# facebard-7-sensor-neopixel-ffc.net
KiCad netlist of a schematic drawn in EAGLE
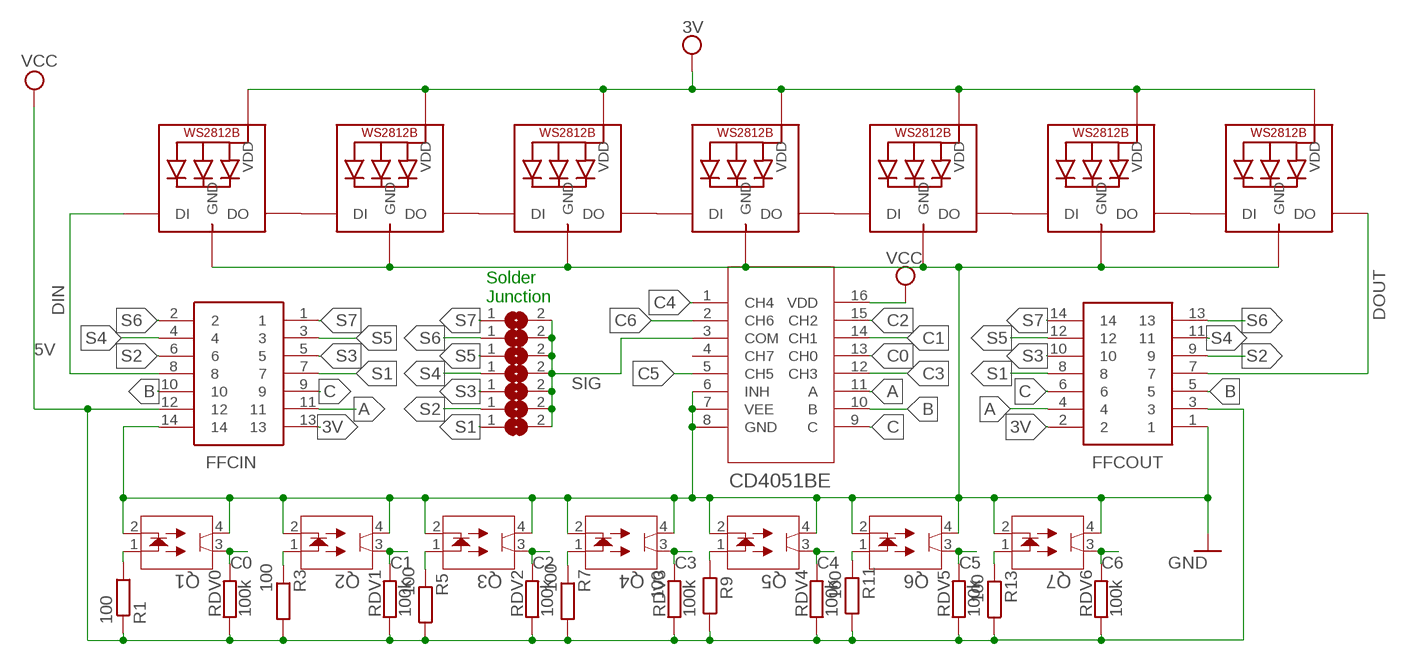
[diagram p0: schematic, sheet 1]

(export (version "E")
  (design (tool "Eeschema 10.0.6"))
  (components
    (comp (ref "FFCIN")
      (value "52806-1410")
      (footprint "eagle-import:528061410")
      (fields (field (name "MOUSER_PART_NUMBER") "538-52806-1410"))
      (libsource (lib "eagle-import") (part "52806-1410"))
    )
    (comp (ref "FFCOUT")
      (value "52806-1410")
      (footprint "eagle-import:528061410")
      (fields (field (name "MOUSER_PART_NUMBER") "538-52806-1410"))
      (libsource (lib "eagle-import") (part "52806-1410"))
    )
    (comp (ref "LED1")
      (value "WS2812B3535")
      (footprint "eagle-import:LED3535")
      (libsource (lib "eagle-import") (part "WS2812B3535"))
    )
    (comp (ref "LED2")
      (value "WS2812B3535")
      (footprint "eagle-import:LED3535")
      (libsource (lib "eagle-import") (part "WS2812B3535"))
    )
    (comp (ref "LED3")
      (value "WS2812B3535")
      (footprint "eagle-import:LED3535")
      (libsource (lib "eagle-import") (part "WS2812B3535"))
    )
    (comp (ref "LED4")
      (value "WS2812B3535")
      (footprint "eagle-import:LED3535")
      (libsource (lib "eagle-import") (part "WS2812B3535"))
    )
    (comp (ref "LED5")
      (value "WS2812B3535")
      (footprint "eagle-import:LED3535")
      (libsource (lib "eagle-import") (part "WS2812B3535"))
    )
    (comp (ref "LED6")
      (value "WS2812B3535")
      (footprint "eagle-import:LED3535")
      (libsource (lib "eagle-import") (part "WS2812B3535"))
    )
    (comp (ref "LED7")
      (value "WS2812B3535")
      (footprint "eagle-import:LED3535")
      (libsource (lib "eagle-import") (part "WS2812B3535"))
    )
    (comp (ref "Q1")
      (value "QRE1113")
      (footprint "eagle-import:DIP4_100AQ_ONS")
      (fields (field (name "COPYRIGHT") "Copyright (C) 2024 Ultra Librarian. All rights reserved."))
      (libsource (lib "eagle-import") (part "QRE1113"))
    )
    (comp (ref "Q2")
      (value "QRE1113")
      (footprint "eagle-import:DIP4_100AQ_ONS")
      (fields (field (name "COPYRIGHT") "Copyright (C) 2024 Ultra Librarian. All rights reserved."))
      (libsource (lib "eagle-import") (part "QRE1113"))
    )
    (comp (ref "Q3")
      (value "QRE1113")
      (footprint "eagle-import:DIP4_100AQ_ONS")
      (fields (field (name "COPYRIGHT") "Copyright (C) 2024 Ultra Librarian. All rights reserved."))
      (libsource (lib "eagle-import") (part "QRE1113"))
    )
    (comp (ref "Q4")
      (value "QRE1113")
      (footprint "eagle-import:DIP4_100AQ_ONS")
      (fields (field (name "COPYRIGHT") "Copyright (C) 2024 Ultra Librarian. All rights reserved."))
      (libsource (lib "eagle-import") (part "QRE1113"))
    )
    (comp (ref "Q5")
      (value "QRE1113")
      (footprint "eagle-import:DIP4_100AQ_ONS")
      (fields (field (name "COPYRIGHT") "Copyright (C) 2024 Ultra Librarian. All rights reserved."))
      (libsource (lib "eagle-import") (part "QRE1113"))
    )
    (comp (ref "Q6")
      (value "QRE1113")
      (footprint "eagle-import:DIP4_100AQ_ONS")
      (fields (field (name "COPYRIGHT") "Copyright (C) 2024 Ultra Librarian. All rights reserved."))
      (libsource (lib "eagle-import") (part "QRE1113"))
    )
    (comp (ref "Q7")
      (value "QRE1113")
      (footprint "eagle-import:DIP4_100AQ_ONS")
      (fields (field (name "COPYRIGHT") "Copyright (C) 2024 Ultra Librarian. All rights reserved."))
      (libsource (lib "eagle-import") (part "QRE1113"))
    )
    (comp (ref "R1")
      (value "100")
      (footprint "eagle-import:0207_10")
      (libsource (lib "eagle-import") (part "R-EU_0207/10"))
    )
    (comp (ref "R3")
      (value "100")
      (footprint "eagle-import:0207_10")
      (libsource (lib "eagle-import") (part "R-EU_0207/10"))
    )
    (comp (ref "R5")
      (value "100")
      (footprint "eagle-import:0207_10")
      (libsource (lib "eagle-import") (part "R-EU_0207/10"))
    )
    (comp (ref "R7")
      (value "100")
      (footprint "eagle-import:0207_10")
      (libsource (lib "eagle-import") (part "R-EU_0207/10"))
    )
    (comp (ref "R9")
      (value "100")
      (footprint "eagle-import:0207_10")
      (libsource (lib "eagle-import") (part "R-EU_0207/10"))
    )
    (comp (ref "R11")
      (value "100")
      (footprint "eagle-import:0207_10")
      (libsource (lib "eagle-import") (part "R-EU_0207/10"))
    )
    (comp (ref "R13")
      (value "100")
      (footprint "eagle-import:0207_10")
      (libsource (lib "eagle-import") (part "R-EU_0207/10"))
    )
    (comp (ref "RDV0")
      (value "100k")
      (footprint "eagle-import:0207_10")
      (libsource (lib "eagle-import") (part "R-EU_0207/10"))
    )
    (comp (ref "RDV1")
      (value "100k")
      (footprint "eagle-import:0207_10")
      (libsource (lib "eagle-import") (part "R-EU_0207/10"))
    )
    (comp (ref "RDV2")
      (value "100k")
      (footprint "eagle-import:0207_10")
      (libsource (lib "eagle-import") (part "R-EU_0207/10"))
    )
    (comp (ref "RDV3")
      (value "100k")
      (footprint "eagle-import:0207_10")
      (libsource (lib "eagle-import") (part "R-EU_0207/10"))
    )
    (comp (ref "RDV4")
      (value "100k")
      (footprint "eagle-import:0207_10")
      (libsource (lib "eagle-import") (part "R-EU_0207/10"))
    )
    (comp (ref "RDV5")
      (value "100k")
      (footprint "eagle-import:0207_10")
      (libsource (lib "eagle-import") (part "R-EU_0207/10"))
    )
    (comp (ref "RDV6")
      (value "100k")
      (footprint "eagle-import:0207_10")
      (libsource (lib "eagle-import") (part "R-EU_0207/10"))
    )
    (comp (ref "SJ1") (value "SJ") (footprint "eagle-import:SJ") (libsource (lib "eagle-import") (part "SJ")))
    (comp (ref "SJ2") (value "SJ") (footprint "eagle-import:SJ") (libsource (lib "eagle-import") (part "SJ")))
    (comp (ref "SJ3") (value "SJ") (footprint "eagle-import:SJ") (libsource (lib "eagle-import") (part "SJ")))
    (comp (ref "SJ4") (value "SJ") (footprint "eagle-import:SJ") (libsource (lib "eagle-import") (part "SJ")))
    (comp (ref "SJ5") (value "SJ") (footprint "eagle-import:SJ") (libsource (lib "eagle-import") (part "SJ")))
    (comp (ref "SJ6") (value "SJ") (footprint "eagle-import:SJ") (libsource (lib "eagle-import") (part "SJ")))
    (comp (ref "SJ7") (value "SJ") (footprint "eagle-import:SJ") (libsource (lib "eagle-import") (part "SJ")))
    (comp (ref "U1")
      (value "CD4051BE")
      (footprint "eagle-import:N16")
      (fields (field (name "COPYRIGHT") "Copyright (C) 2024 Ultra Librarian. All rights reserved."))
      (libsource (lib "eagle-import") (part "CD4051BE"))
    )
  )
  (nets
    (net (code "1") (name "/DIN") (class "Default")
      (node (ref "FFCIN") (pin "8") (pinfunction "8_8") (pintype "bidirectional"))
      (node (ref "LED1") (pin "1") (pinfunction "DI_1") (pintype "input"))
    )
    (net (code "2") (name "/DOUT") (class "Default")
      (node (ref "FFCOUT") (pin "7") (pinfunction "7_7") (pintype "bidirectional"))
      (node (ref "LED7") (pin "3") (pinfunction "DO_3") (pintype "output"))
    )
    (net (code "3") (name "/SIG") (class "Default")
      (node (ref "SJ1") (pin "2") (pinfunction "2_2") (pintype "passive"))
      (node (ref "SJ2") (pin "2") (pinfunction "2_2") (pintype "passive"))
      (node (ref "SJ3") (pin "2") (pinfunction "2_2") (pintype "passive"))
      (node (ref "SJ4") (pin "2") (pinfunction "2_2") (pintype "passive"))
      (node (ref "SJ5") (pin "2") (pinfunction "2_2") (pintype "passive"))
      (node (ref "SJ6") (pin "2") (pinfunction "2_2") (pintype "passive"))
      (node (ref "SJ7") (pin "2") (pinfunction "2_2") (pintype "passive"))
      (node (ref "U1") (pin "3") (pinfunction "COM_3") (pintype "bidirectional"))
    )
    (net (code "4") (name "3V") (class "Default")
      (node (ref "FFCIN") (pin "13") (pinfunction "13_13") (pintype "bidirectional"))
      (node (ref "FFCOUT") (pin "2") (pinfunction "2_2") (pintype "bidirectional"))
      (node (ref "LED1") (pin "2") (pinfunction "VDD_2") (pintype "power_in"))
      (node (ref "LED2") (pin "2") (pinfunction "VDD_2") (pintype "power_in"))
      (node (ref "LED3") (pin "2") (pinfunction "VDD_2") (pintype "power_in"))
      (node (ref "LED4") (pin "2") (pinfunction "VDD_2") (pintype "power_in"))
      (node (ref "LED5") (pin "2") (pinfunction "VDD_2") (pintype "power_in"))
      (node (ref "LED6") (pin "2") (pinfunction "VDD_2") (pintype "power_in"))
      (node (ref "LED7") (pin "2") (pinfunction "VDD_2") (pintype "power_in"))
    )
    (net (code "5") (name "A") (class "Default")
      (node (ref "FFCIN") (pin "11") (pinfunction "11_11") (pintype "bidirectional"))
      (node (ref "FFCOUT") (pin "4") (pinfunction "4_4") (pintype "bidirectional"))
      (node (ref "U1") (pin "11") (pinfunction "A_11") (pintype "passive"))
    )
    (net (code "6") (name "B") (class "Default")
      (node (ref "FFCIN") (pin "10") (pinfunction "10_10") (pintype "bidirectional"))
      (node (ref "FFCOUT") (pin "5") (pinfunction "5_5") (pintype "bidirectional"))
      (node (ref "U1") (pin "10") (pinfunction "B_10") (pintype "passive"))
    )
    (net (code "7") (name "C") (class "Default")
      (node (ref "FFCIN") (pin "9") (pinfunction "9_9") (pintype "bidirectional"))
      (node (ref "FFCOUT") (pin "6") (pinfunction "6_6") (pintype "bidirectional"))
      (node (ref "U1") (pin "9") (pinfunction "C_9") (pintype "passive"))
    )
    (net (code "8") (name "C0") (class "Default")
      (node (ref "Q1") (pin "3") (pinfunction "3_3") (pintype "passive"))
      (node (ref "RDV0") (pin "2") (pinfunction "2_2") (pintype "passive"))
      (node (ref "U1") (pin "13") (pinfunction "CH0_13") (pintype "bidirectional"))
    )
    (net (code "9") (name "C1") (class "Default")
      (node (ref "Q2") (pin "3") (pinfunction "3_3") (pintype "passive"))
      (node (ref "RDV1") (pin "2") (pinfunction "2_2") (pintype "passive"))
      (node (ref "U1") (pin "14") (pinfunction "CH1_14") (pintype "bidirectional"))
    )
    (net (code "10") (name "C2") (class "Default")
      (node (ref "Q3") (pin "3") (pinfunction "3_3") (pintype "passive"))
      (node (ref "RDV2") (pin "2") (pinfunction "2_2") (pintype "passive"))
      (node (ref "U1") (pin "15") (pinfunction "CH2_15") (pintype "bidirectional"))
    )
    (net (code "11") (name "C3") (class "Default")
      (node (ref "Q4") (pin "3") (pinfunction "3_3") (pintype "passive"))
      (node (ref "RDV3") (pin "2") (pinfunction "2_2") (pintype "passive"))
      (node (ref "U1") (pin "12") (pinfunction "CH3_12") (pintype "bidirectional"))
    )
    (net (code "12") (name "C4") (class "Default")
      (node (ref "Q5") (pin "3") (pinfunction "3_3") (pintype "passive"))
      (node (ref "RDV4") (pin "2") (pinfunction "2_2") (pintype "passive"))
      (node (ref "U1") (pin "1") (pinfunction "CH4_1") (pintype "bidirectional"))
    )
    (net (code "13") (name "C5") (class "Default")
      (node (ref "Q6") (pin "3") (pinfunction "3_3") (pintype "passive"))
      (node (ref "RDV5") (pin "2") (pinfunction "2_2") (pintype "passive"))
      (node (ref "U1") (pin "5") (pinfunction "CH5_5") (pintype "bidirectional"))
    )
    (net (code "14") (name "C6") (class "Default")
      (node (ref "Q7") (pin "3") (pinfunction "3_3") (pintype "passive"))
      (node (ref "RDV6") (pin "2") (pinfunction "2_2") (pintype "passive"))
      (node (ref "U1") (pin "2") (pinfunction "CH6_2") (pintype "bidirectional"))
    )
    (net (code "15") (name "GND") (class "Default")
      (node (ref "FFCIN") (pin "14") (pinfunction "14_14") (pintype "bidirectional"))
      (node (ref "FFCOUT") (pin "1") (pinfunction "1_1") (pintype "bidirectional"))
      (node (ref "LED1") (pin "4") (pinfunction "GND_4") (pintype "power_in"))
      (node (ref "LED2") (pin "4") (pinfunction "GND_4") (pintype "power_in"))
      (node (ref "LED3") (pin "4") (pinfunction "GND_4") (pintype "power_in"))
      (node (ref "LED4") (pin "4") (pinfunction "GND_4") (pintype "power_in"))
      (node (ref "LED5") (pin "4") (pinfunction "GND_4") (pintype "power_in"))
      (node (ref "LED6") (pin "4") (pinfunction "GND_4") (pintype "power_in"))
      (node (ref "LED7") (pin "4") (pinfunction "GND_4") (pintype "power_in"))
      (node (ref "Q1") (pin "2") (pinfunction "2_2") (pintype "passive"))
      (node (ref "Q1") (pin "4") (pinfunction "4_4") (pintype "passive"))
      (node (ref "Q2") (pin "2") (pinfunction "2_2") (pintype "passive"))
      (node (ref "Q2") (pin "4") (pinfunction "4_4") (pintype "passive"))
      (node (ref "Q3") (pin "2") (pinfunction "2_2") (pintype "passive"))
      (node (ref "Q3") (pin "4") (pinfunction "4_4") (pintype "passive"))
      (node (ref "Q4") (pin "2") (pinfunction "2_2") (pintype "passive"))
      (node (ref "Q4") (pin "4") (pinfunction "4_4") (pintype "passive"))
      (node (ref "Q5") (pin "2") (pinfunction "2_2") (pintype "passive"))
      (node (ref "Q5") (pin "4") (pinfunction "4_4") (pintype "passive"))
      (node (ref "Q6") (pin "2") (pinfunction "2_2") (pintype "passive"))
      (node (ref "Q6") (pin "4") (pinfunction "4_4") (pintype "passive"))
      (node (ref "Q7") (pin "2") (pinfunction "2_2") (pintype "passive"))
      (node (ref "Q7") (pin "4") (pinfunction "4_4") (pintype "passive"))
      (node (ref "U1") (pin "6") (pinfunction "INH_6") (pintype "passive"))
      (node (ref "U1") (pin "7") (pinfunction "VEE_7") (pintype "power_in"))
      (node (ref "U1") (pin "8") (pinfunction "GND_8") (pintype "power_in"))
    )
    (net (code "16") (name "Net-(LED1-DO)") (class "Default")
      (node (ref "LED1") (pin "3") (pinfunction "DO_3") (pintype "output"))
      (node (ref "LED2") (pin "1") (pinfunction "DI_1") (pintype "input"))
    )
    (net (code "17") (name "Net-(LED2-DO)") (class "Default")
      (node (ref "LED2") (pin "3") (pinfunction "DO_3") (pintype "output"))
      (node (ref "LED3") (pin "1") (pinfunction "DI_1") (pintype "input"))
    )
    (net (code "18") (name "Net-(LED3-DO)") (class "Default")
      (node (ref "LED3") (pin "3") (pinfunction "DO_3") (pintype "output"))
      (node (ref "LED4") (pin "1") (pinfunction "DI_1") (pintype "input"))
    )
    (net (code "19") (name "Net-(LED4-DO)") (class "Default")
      (node (ref "LED4") (pin "3") (pinfunction "DO_3") (pintype "output"))
      (node (ref "LED5") (pin "1") (pinfunction "DI_1") (pintype "input"))
    )
    (net (code "20") (name "Net-(LED5-DO)") (class "Default")
      (node (ref "LED5") (pin "3") (pinfunction "DO_3") (pintype "output"))
      (node (ref "LED6") (pin "1") (pinfunction "DI_1") (pintype "input"))
    )
    (net (code "21") (name "Net-(LED6-DO)") (class "Default")
      (node (ref "LED6") (pin "3") (pinfunction "DO_3") (pintype "output"))
      (node (ref "LED7") (pin "1") (pinfunction "DI_1") (pintype "input"))
    )
    (net (code "22") (name "Net-(Q1-Pad1)") (class "Default")
      (node (ref "Q1") (pin "1") (pinfunction "1_1") (pintype "passive"))
      (node (ref "R1") (pin "2") (pinfunction "2_2") (pintype "passive"))
    )
    (net (code "23") (name "Net-(Q2-Pad1)") (class "Default")
      (node (ref "Q2") (pin "1") (pinfunction "1_1") (pintype "passive"))
      (node (ref "R3") (pin "2") (pinfunction "2_2") (pintype "passive"))
    )
    (net (code "24") (name "Net-(Q3-Pad1)") (class "Default")
      (node (ref "Q3") (pin "1") (pinfunction "1_1") (pintype "passive"))
      (node (ref "R5") (pin "2") (pinfunction "2_2") (pintype "passive"))
    )
    (net (code "25") (name "Net-(Q4-Pad1)") (class "Default")
      (node (ref "Q4") (pin "1") (pinfunction "1_1") (pintype "passive"))
      (node (ref "R7") (pin "2") (pinfunction "2_2") (pintype "passive"))
    )
    (net (code "26") (name "Net-(Q5-Pad1)") (class "Default")
      (node (ref "Q5") (pin "1") (pinfunction "1_1") (pintype "passive"))
      (node (ref "R9") (pin "2") (pinfunction "2_2") (pintype "passive"))
    )
    (net (code "27") (name "Net-(Q6-Pad1)") (class "Default")
      (node (ref "Q6") (pin "1") (pinfunction "1_1") (pintype "passive"))
      (node (ref "R11") (pin "2") (pinfunction "2_2") (pintype "passive"))
    )
    (net (code "28") (name "Net-(Q7-Pad1)") (class "Default")
      (node (ref "Q7") (pin "1") (pinfunction "1_1") (pintype "passive"))
      (node (ref "R13") (pin "2") (pinfunction "2_2") (pintype "passive"))
    )
    (net (code "29") (name "S1") (class "Default")
      (node (ref "FFCIN") (pin "7") (pinfunction "7_7") (pintype "bidirectional"))
      (node (ref "FFCOUT") (pin "8") (pinfunction "8_8") (pintype "bidirectional"))
      (node (ref "SJ1") (pin "1") (pinfunction "1_1") (pintype "passive"))
    )
    (net (code "30") (name "S2") (class "Default")
      (node (ref "FFCIN") (pin "6") (pinfunction "6_6") (pintype "bidirectional"))
      (node (ref "FFCOUT") (pin "9") (pinfunction "9_9") (pintype "bidirectional"))
      (node (ref "SJ2") (pin "1") (pinfunction "1_1") (pintype "passive"))
    )
    (net (code "31") (name "S3") (class "Default")
      (node (ref "FFCIN") (pin "5") (pinfunction "5_5") (pintype "bidirectional"))
      (node (ref "FFCOUT") (pin "10") (pinfunction "10_10") (pintype "bidirectional"))
      (node (ref "SJ3") (pin "1") (pinfunction "1_1") (pintype "passive"))
    )
    (net (code "32") (name "S4") (class "Default")
      (node (ref "FFCIN") (pin "4") (pinfunction "4_4") (pintype "bidirectional"))
      (node (ref "FFCOUT") (pin "11") (pinfunction "11_11") (pintype "bidirectional"))
      (node (ref "SJ4") (pin "1") (pinfunction "1_1") (pintype "passive"))
    )
    (net (code "33") (name "S5") (class "Default")
      (node (ref "FFCIN") (pin "3") (pinfunction "3_3") (pintype "bidirectional"))
      (node (ref "FFCOUT") (pin "12") (pinfunction "12_12") (pintype "bidirectional"))
      (node (ref "SJ5") (pin "1") (pinfunction "1_1") (pintype "passive"))
    )
    (net (code "34") (name "S6") (class "Default")
      (node (ref "FFCIN") (pin "2") (pinfunction "2_2") (pintype "bidirectional"))
      (node (ref "FFCOUT") (pin "13") (pinfunction "13_13") (pintype "bidirectional"))
      (node (ref "SJ6") (pin "1") (pinfunction "1_1") (pintype "passive"))
    )
    (net (code "35") (name "S7") (class "Default")
      (node (ref "FFCIN") (pin "1") (pinfunction "1_1") (pintype "bidirectional"))
      (node (ref "FFCOUT") (pin "14") (pinfunction "14_14") (pintype "bidirectional"))
      (node (ref "SJ7") (pin "1") (pinfunction "1_1") (pintype "passive"))
    )
    (net (code "36") (name "VCC") (class "Default")
      (node (ref "FFCIN") (pin "12") (pinfunction "12_12") (pintype "bidirectional"))
      (node (ref "FFCOUT") (pin "3") (pinfunction "3_3") (pintype "bidirectional"))
      (node (ref "R1") (pin "1") (pinfunction "1_1") (pintype "passive"))
      (node (ref "R11") (pin "1") (pinfunction "1_1") (pintype "passive"))
      (node (ref "R13") (pin "1") (pinfunction "1_1") (pintype "passive"))
      (node (ref "R3") (pin "1") (pinfunction "1_1") (pintype "passive"))
      (node (ref "R5") (pin "1") (pinfunction "1_1") (pintype "passive"))
      (node (ref "R7") (pin "1") (pinfunction "1_1") (pintype "passive"))
      (node (ref "R9") (pin "1") (pinfunction "1_1") (pintype "passive"))
      (node (ref "RDV0") (pin "1") (pinfunction "1_1") (pintype "passive"))
      (node (ref "RDV1") (pin "1") (pinfunction "1_1") (pintype "passive"))
      (node (ref "RDV2") (pin "1") (pinfunction "1_1") (pintype "passive"))
      (node (ref "RDV3") (pin "1") (pinfunction "1_1") (pintype "passive"))
      (node (ref "RDV4") (pin "1") (pinfunction "1_1") (pintype "passive"))
      (node (ref "RDV5") (pin "1") (pinfunction "1_1") (pintype "passive"))
      (node (ref "RDV6") (pin "1") (pinfunction "1_1") (pintype "passive"))
      (node (ref "U1") (pin "16") (pinfunction "VDD_16") (pintype "power_in"))
    )
    (net (code "37") (name "unconnected-(U1-CH7-Pad4)") (class "Default")
      (node (ref "U1") (pin "4") (pinfunction "CH7_4") (pintype "bidirectional"))
    )
  )
)
